# Test101.net
KiCad netlist of a schematic drawn in EAGLE
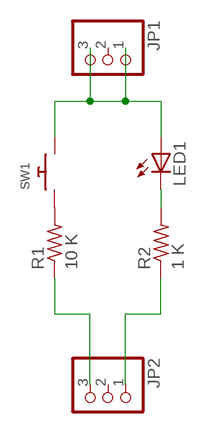
[diagram p0: schematic, sheet 1]

(export (version "E")
  (design (tool "Eeschema 10.0.6"))
  (components
    (comp (ref "JP1")
      (value "PINHD-1X3")
      (footprint "eagle-import:1X03")
      (libsource (lib "eagle-import") (part "PINHD-1X3"))
    )
    (comp (ref "JP2")
      (value "PINHD-1X3")
      (footprint "eagle-import:1X03")
      (libsource (lib "eagle-import") (part "PINHD-1X3"))
    )
    (comp (ref "LED1")
      (value "LED3MM")
      (footprint "eagle-import:LED3MM")
      (libsource (lib "eagle-import") (part "LED3MM"))
    )
    (comp (ref "R1")
      (value "10 K")
      (footprint "eagle-import:0207_7")
      (libsource (lib "eagle-import") (part "R-US_0207/7"))
    )
    (comp (ref "R2")
      (value "1 K")
      (footprint "eagle-import:0207_7")
      (libsource (lib "eagle-import") (part "R-US_0207/7"))
    )
    (comp (ref "SW1")
      (value "SWITCH_PUSHBUTTONEVQ-PE")
      (footprint "eagle-import:TACT_PANA-EVQ")
      (libsource (lib "eagle-import") (part "SWITCH_PUSHBUTTONEVQ-PE"))
    )
  )
  (nets
    (net (code "1") (name "Net-(JP1-Pad1)") (class "Default")
      (node (ref "JP1") (pin "1") (pinfunction "1_1") (pintype "passive"))
      (node (ref "JP1") (pin "3") (pinfunction "3_3") (pintype "passive"))
      (node (ref "LED1") (pin "A") (pinfunction "A_A") (pintype "passive"))
      (node (ref "SW1") (pin "P$2") (pinfunction "P$2_P$2") (pintype "passive"))
    )
    (net (code "2") (name "Net-(JP2-Pad1)") (class "Default")
      (node (ref "JP2") (pin "1") (pinfunction "1_1") (pintype "passive"))
      (node (ref "R2") (pin "1") (pinfunction "1_1") (pintype "passive"))
    )
    (net (code "3") (name "Net-(JP2-Pad3)") (class "Default")
      (node (ref "JP2") (pin "3") (pinfunction "3_3") (pintype "passive"))
      (node (ref "R1") (pin "1") (pinfunction "1_1") (pintype "passive"))
    )
    (net (code "4") (name "Net-(LED1-C)") (class "Default")
      (node (ref "LED1") (pin "K") (pinfunction "C_K") (pintype "passive"))
      (node (ref "R2") (pin "2") (pinfunction "2_2") (pintype "passive"))
    )
    (net (code "5") (name "Net-(R1-Pad2)") (class "Default")
      (node (ref "R1") (pin "2") (pinfunction "2_2") (pintype "passive"))
      (node (ref "SW1") (pin "P$1") (pinfunction "P$1_P$1") (pintype "passive"))
    )
    (net (code "6") (name "unconnected-(JP1-Pad2)") (class "Default")
      (node (ref "JP1") (pin "2") (pinfunction "2_2") (pintype "passive"))
    )
    (net (code "7") (name "unconnected-(JP2-Pad2)") (class "Default")
      (node (ref "JP2") (pin "2") (pinfunction "2_2") (pintype "passive"))
    )
  )
)
